# Boost_Converter_10V.net
KiCad netlist of a schematic drawn in Altium Designer
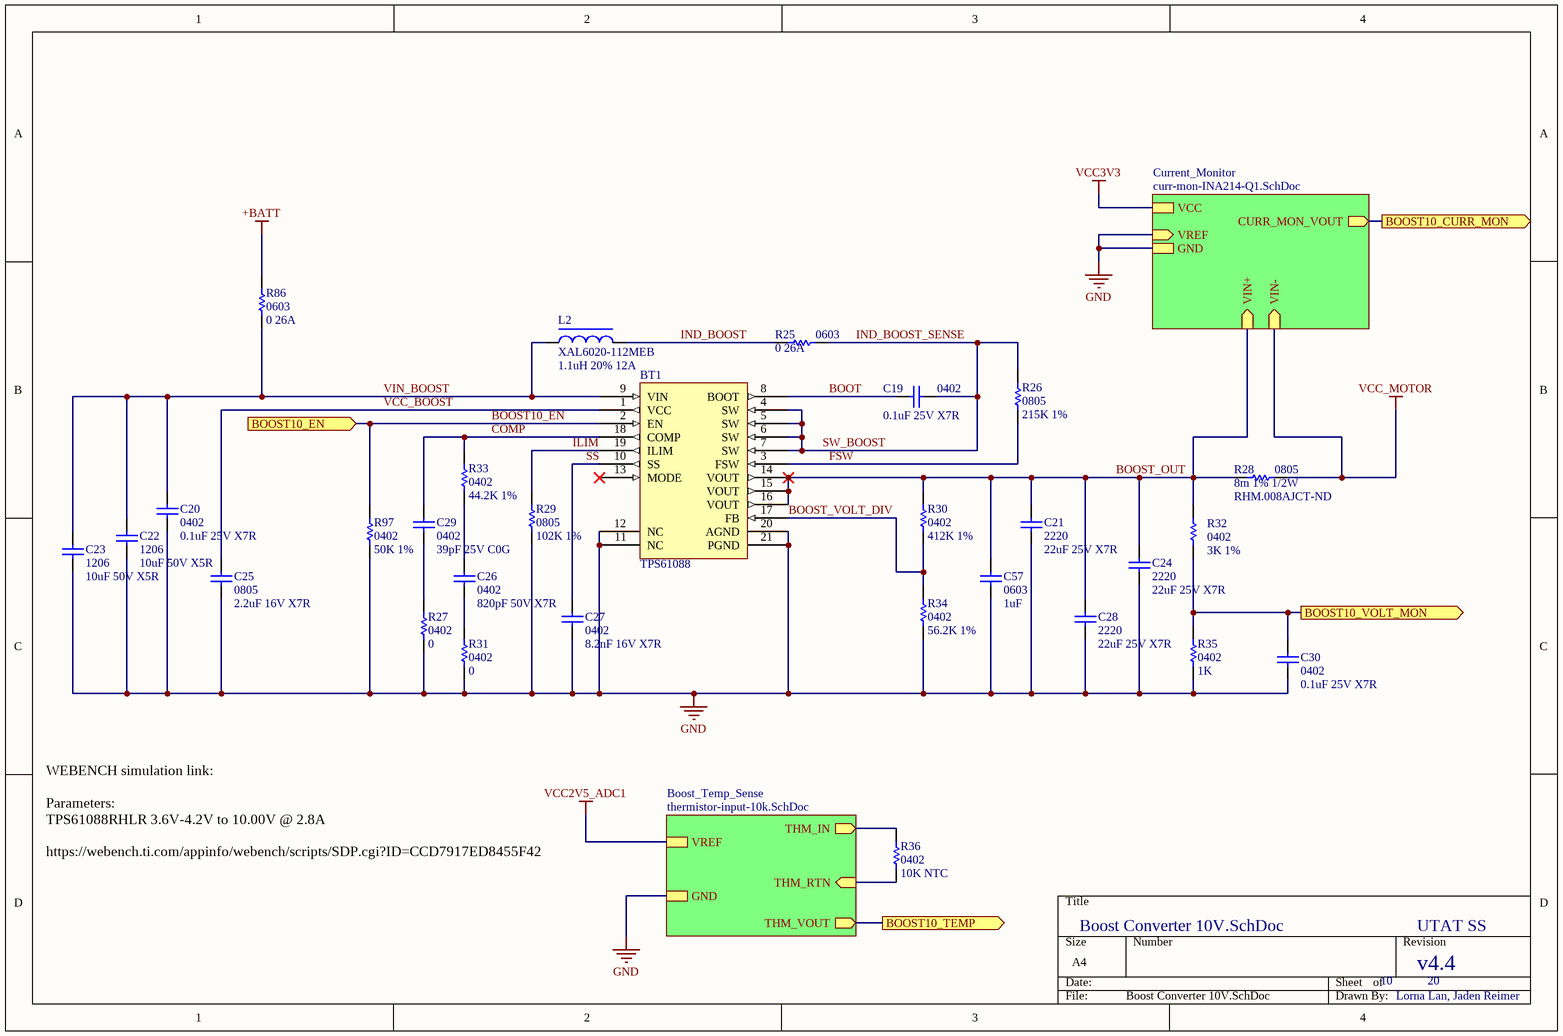
[diagram p0: Boost Converter 10V.SchDoc]

(export (version "E")
  (design (tool "Eeschema 10.0.6"))
  (components
    (comp (ref "BT1")
      (value "TPS61088")
      (footprint "QFN50P450X350X100-21N")
      (description "Boost converter")
      (libsource (lib "EPS") (part "TPS61088"))
    )
    (comp (ref "C19")
      (value "0402")
      (footprint "CAP0402R")
      (description "0402 capacitor")
      (fields (field (name "ALTIUM_VALUE") "0.1uF 25V X7R"))
      (libsource (lib "heron-general") (part "CAP0402"))
    )
    (comp (ref "C20")
      (value "0402")
      (footprint "CAP0402R")
      (description "0402 capacitor")
      (fields (field (name "ALTIUM_VALUE") "0.1uF 25V X7R"))
      (libsource (lib "heron-general") (part "CAP0402"))
    )
    (comp (ref "C21")
      (value "2220")
      (footprint "CAP2220")
      (description "Ceramic Capacitor 2220 (5750 Metric)")
      (fields (field (name "ALTIUM_VALUE") "22uF 25V X7R"))
      (libsource (lib "CAP2220") (part "CAP2220"))
    )
    (comp (ref "C22")
      (value "1206")
      (footprint "CAP1206R")
      (description "1206 capacitor")
      (fields (field (name "ALTIUM_VALUE") "10uF 50V X5R"))
      (libsource (lib "CAP1206") (part "CAP1206"))
    )
    (comp (ref "C23")
      (value "1206")
      (footprint "CAP1206R")
      (description "1206 capacitor")
      (fields (field (name "ALTIUM_VALUE") "10uF 50V X5R"))
      (libsource (lib "CAP1206") (part "CAP1206"))
    )
    (comp (ref "C24")
      (value "2220")
      (footprint "CAP2220")
      (description "Ceramic Capacitor 2220 (5750 Metric)")
      (fields (field (name "ALTIUM_VALUE") "22uF 25V X7R"))
      (libsource (lib "CAP2220") (part "CAP2220"))
    )
    (comp (ref "C25")
      (value "0805")
      (footprint "CAP0805R")
      (description "0805 capacitor")
      (fields (field (name "ALTIUM_VALUE") "2.2uF 16V X7R"))
      (libsource (lib "heron-general") (part "CAP0805"))
    )
    (comp (ref "C26")
      (value "0402")
      (footprint "CAP0402R")
      (description "0402 capacitor")
      (fields (field (name "ALTIUM_VALUE") "820pF 50V X7R"))
      (libsource (lib "CAP0402") (part "CAP0402"))
    )
    (comp (ref "C27")
      (value "0402")
      (footprint "CAP0402R")
      (description "0402 capacitor")
      (fields (field (name "ALTIUM_VALUE") "8.2nF 16V X7R"))
      (libsource (lib "CAP0402") (part "CAP0402"))
    )
    (comp (ref "C28")
      (value "2220")
      (footprint "CAP2220")
      (description "Ceramic Capacitor 2220 (5750 Metric)")
      (fields (field (name "ALTIUM_VALUE") "22uF 25V X7R"))
      (libsource (lib "CAP2220") (part "CAP2220"))
    )
    (comp (ref "C29")
      (value "0402")
      (footprint "CAP0402R")
      (description "0402 capacitor")
      (fields (field (name "ALTIUM_VALUE") "39pF 25V C0G"))
      (libsource (lib "CAP0402") (part "CAP0402"))
    )
    (comp (ref "C30")
      (value "0402")
      (footprint "CAP0402R")
      (description "0402 capacitor")
      (fields (field (name "ALTIUM_VALUE") "0.1uF 25V X7R"))
      (libsource (lib "heron-general") (part "CAP0402"))
    )
    (comp (ref "C57")
      (value "0603")
      (footprint "CAP0603R")
      (description "0603 capacitor")
      (fields
        (field (name "ALTIUM_VALUE") "1uF")
        (field (name "MANUFACTURER") "KEMET")
        (field (name "MANUFACTURER PART NUMBER") "C0603C105K4RACAUTO")
      )
      (libsource (lib "heron-general") (part "CAP0603"))
    )
    (comp (ref "L2")
      (value "XAL6020-112MEB")
      (footprint "XAL6020-112MEB")
      (description "Fixed Inductors 1.1uH 20% 12A, 13.1mOhms AEC-Q200")
      (fields (field (name "ALTIUM_VALUE") "1.1uH 20% 12A"))
      (libsource (lib "heron-general") (part "XAL6020-112MEB"))
    )
    (comp (ref "R25")
      (value "0603")
      (footprint "RES0603R")
      (description "0603 resistor")
      (fields (field (name "ALTIUM_VALUE") "0 26A"))
      (libsource (lib "heron-general") (part "RES0603"))
    )
    (comp (ref "R26")
      (value "0805")
      (footprint "RES0805R")
      (description "0805 resistor")
      (fields (field (name "ALTIUM_VALUE") "215K 1%"))
      (libsource (lib "RES0805") (part "RES0805"))
    )
    (comp (ref "R27")
      (value "0402")
      (footprint "RES0402R")
      (description "0402 resistor")
      (fields
        (field (name "ALTIUM_VALUE") "0")
        (field (name "MANUFACTURER") "Panasonic")
        (field (name "MANUFACTURER PART NUMBER") "ERJ-2GE0R00X")
      )
      (libsource (lib "heron-general") (part "RES0402"))
    )
    (comp (ref "R28")
      (value "0805")
      (footprint "RES0805R")
      (description "0805 resistor")
      (fields
        (field (name "ALTIUM_VALUE") "8m 1% 1/2W")
        (field (name "SUPPLIER PART NUMBER 1") "RHM.008AJCT-ND")
      )
      (libsource (lib "RES0805") (part "RES0805"))
    )
    (comp (ref "R29")
      (value "0805")
      (footprint "RES0805R")
      (description "0805 resistor")
      (fields (field (name "ALTIUM_VALUE") "102K 1%"))
      (libsource (lib "RES0805") (part "RES0805"))
    )
    (comp (ref "R30")
      (value "0402")
      (footprint "RES0402R")
      (description "0402 resistor")
      (fields (field (name "ALTIUM_VALUE") "412K 1%"))
      (libsource (lib "RES0402") (part "RES0402"))
    )
    (comp (ref "R31")
      (value "0402")
      (footprint "RES0402R")
      (description "0402 resistor")
      (fields
        (field (name "ALTIUM_VALUE") "0")
        (field (name "MANUFACTURER") "Panasonic")
        (field (name "MANUFACTURER PART NUMBER") "ERJ-2GE0R00X")
      )
      (libsource (lib "heron-general") (part "RES0402"))
    )
    (comp (ref "R32")
      (value "0402")
      (footprint "RES0402R")
      (description "0402 resistor")
      (fields (field (name "ALTIUM_VALUE") "3K 1%"))
      (libsource (lib "RES0402") (part "RES0402"))
    )
    (comp (ref "R33")
      (value "0402")
      (footprint "RES0402R")
      (description "0402 resistor")
      (fields (field (name "ALTIUM_VALUE") "44.2K 1%"))
      (libsource (lib "heron-general") (part "RES0402"))
    )
    (comp (ref "R34")
      (value "0402")
      (footprint "RES0402R")
      (description "0402 resistor")
      (fields (field (name "ALTIUM_VALUE") "56.2K 1%"))
      (libsource (lib "RES0402") (part "RES0402"))
    )
    (comp (ref "R35")
      (value "0402")
      (footprint "RES0402R")
      (description "0402 resistor")
      (fields (field (name "ALTIUM_VALUE") "1K"))
      (libsource (lib "RES0402") (part "RES0402"))
    )
    (comp (ref "R36")
      (value "0402")
      (footprint "RES0402R")
      (description "0402 resistor")
      (fields (field (name "ALTIUM_VALUE") "10K NTC"))
      (libsource (lib "heron-general") (part "RES0402"))
    )
    (comp (ref "R86")
      (value "0603")
      (footprint "RES0603R")
      (description "0603 resistor")
      (fields (field (name "ALTIUM_VALUE") "0 26A"))
      (libsource (lib "heron-general") (part "RES0603"))
    )
    (comp (ref "R97")
      (value "0402")
      (footprint "RES0402R")
      (description "0402 resistor")
      (fields (field (name "ALTIUM_VALUE") "50K 1%"))
      (libsource (lib "heron-general") (part "RES0402"))
    )
  )
  (nets
    (net (code "1") (name "+BATT") (class "Default")
      (node (ref "R86") (pin "2") (pinfunction "2_2") (pintype "passive"))
    )
    (net (code "3") (name "/BOOST10_EN") (class "Default")
      (node (ref "BT1") (pin "2") (pinfunction "EN_2") (pintype "input"))
      (node (ref "R97") (pin "2") (pinfunction "2_2") (pintype "passive"))
    )
    (net (code "5") (name "/BOOST10_VOLT_MON") (class "Default")
      (node (ref "C30") (pin "2") (pinfunction "2_2") (pintype "passive"))
      (node (ref "R32") (pin "1") (pinfunction "1_1") (pintype "passive"))
      (node (ref "R35") (pin "2") (pinfunction "2_2") (pintype "passive"))
    )
    (net (code "6") (name "/BOOST_OUT") (class "Default")
      (node (ref "BT1") (pin "14") (pinfunction "VOUT_14") (pintype "output"))
      (node (ref "BT1") (pin "15") (pinfunction "VOUT_15") (pintype "output"))
      (node (ref "BT1") (pin "16") (pinfunction "VOUT_16") (pintype "output"))
      (node (ref "C21") (pin "2") (pinfunction "2_2") (pintype "passive"))
      (node (ref "C24") (pin "2") (pinfunction "2_2") (pintype "passive"))
      (node (ref "C28") (pin "2") (pinfunction "2_2") (pintype "passive"))
      (node (ref "C57") (pin "2") (pinfunction "2_2") (pintype "passive"))
      (node (ref "R28") (pin "1") (pinfunction "1_1") (pintype "passive"))
      (node (ref "R30") (pin "2") (pinfunction "2_2") (pintype "passive"))
      (node (ref "R32") (pin "2") (pinfunction "2_2") (pintype "passive"))
    )
    (net (code "7") (name "/BOOST_VOLT_DIV") (class "Default")
      (node (ref "BT1") (pin "17") (pinfunction "FB_17") (pintype "input"))
      (node (ref "R30") (pin "1") (pinfunction "1_1") (pintype "passive"))
      (node (ref "R34") (pin "2") (pinfunction "2_2") (pintype "passive"))
    )
    (net (code "8") (name "/BOOT") (class "Default")
      (node (ref "BT1") (pin "8") (pinfunction "BOOT_8") (pintype "output"))
      (node (ref "C19") (pin "2") (pinfunction "2_2") (pintype "passive"))
    )
    (net (code "9") (name "/COMP") (class "Default")
      (node (ref "BT1") (pin "18") (pinfunction "COMP_18") (pintype "output"))
      (node (ref "C29") (pin "2") (pinfunction "2_2") (pintype "passive"))
      (node (ref "R33") (pin "2") (pinfunction "2_2") (pintype "passive"))
    )
    (net (code "10") (name "/FSW") (class "Default")
      (node (ref "BT1") (pin "3") (pinfunction "FSW_3") (pintype "input"))
      (node (ref "R26") (pin "1") (pinfunction "1_1") (pintype "passive"))
    )
    (net (code "11") (name "/ILIM") (class "Default")
      (node (ref "BT1") (pin "19") (pinfunction "ILIM_19") (pintype "output"))
      (node (ref "R29") (pin "2") (pinfunction "2_2") (pintype "passive"))
    )
    (net (code "12") (name "/IND_BOOST") (class "Default")
      (node (ref "L2") (pin "2") (pinfunction "2_2") (pintype "passive"))
      (node (ref "R25") (pin "1") (pinfunction "1_1") (pintype "passive"))
    )
    (net (code "13") (name "/IND_BOOST_SENSE") (class "Default")
      (node (ref "BT1") (pin "4") (pinfunction "SW_4") (pintype "input"))
      (node (ref "BT1") (pin "5") (pinfunction "SW_5") (pintype "input"))
      (node (ref "BT1") (pin "6") (pinfunction "SW_6") (pintype "input"))
      (node (ref "BT1") (pin "7") (pinfunction "SW_7") (pintype "input"))
      (node (ref "C19") (pin "1") (pinfunction "1_1") (pintype "passive"))
      (node (ref "R25") (pin "2") (pinfunction "2_2") (pintype "passive"))
      (node (ref "R26") (pin "2") (pinfunction "2_2") (pintype "passive"))
    )
    (net (code "14") (name "/SS") (class "Default")
      (node (ref "BT1") (pin "10") (pinfunction "SS_10") (pintype "output"))
      (node (ref "C27") (pin "2") (pinfunction "2_2") (pintype "passive"))
    )
    (net (code "15") (name "/THM_IN") (class "Default")
      (node (ref "R36") (pin "2") (pinfunction "2_2") (pintype "passive"))
    )
    (net (code "16") (name "/THM_RTN") (class "Default")
      (node (ref "R36") (pin "1") (pinfunction "1_1") (pintype "passive"))
    )
    (net (code "17") (name "/VCC_BOOST") (class "Default")
      (node (ref "BT1") (pin "1") (pinfunction "VCC_1") (pintype "output"))
      (node (ref "C25") (pin "2") (pinfunction "2_2") (pintype "passive"))
    )
    (net (code "18") (name "/VIN_BOOST") (class "Default")
      (node (ref "BT1") (pin "9") (pinfunction "VIN_9") (pintype "input"))
      (node (ref "C20") (pin "2") (pinfunction "2_2") (pintype "passive"))
      (node (ref "C22") (pin "2") (pinfunction "2_2") (pintype "passive"))
      (node (ref "C23") (pin "2") (pinfunction "2_2") (pintype "passive"))
      (node (ref "L2") (pin "1") (pinfunction "1_1") (pintype "passive"))
      (node (ref "R86") (pin "1") (pinfunction "1_1") (pintype "passive"))
    )
    (net (code "19") (name "GND") (class "Default")
      (node (ref "BT1") (pin "11") (pinfunction "NC_11") (pintype "passive"))
      (node (ref "BT1") (pin "12") (pinfunction "NC_12") (pintype "passive"))
      (node (ref "BT1") (pin "20") (pinfunction "AGND_20") (pintype "power_in"))
      (node (ref "BT1") (pin "21") (pinfunction "PGND_21") (pintype "power_in"))
      (node (ref "C20") (pin "1") (pinfunction "1_1") (pintype "passive"))
      (node (ref "C21") (pin "1") (pinfunction "1_1") (pintype "passive"))
      (node (ref "C22") (pin "1") (pinfunction "1_1") (pintype "passive"))
      (node (ref "C23") (pin "1") (pinfunction "1_1") (pintype "passive"))
      (node (ref "C24") (pin "1") (pinfunction "1_1") (pintype "passive"))
      (node (ref "C25") (pin "1") (pinfunction "1_1") (pintype "passive"))
      (node (ref "C27") (pin "1") (pinfunction "1_1") (pintype "passive"))
      (node (ref "C28") (pin "1") (pinfunction "1_1") (pintype "passive"))
      (node (ref "C30") (pin "1") (pinfunction "1_1") (pintype "passive"))
      (node (ref "C57") (pin "1") (pinfunction "1_1") (pintype "passive"))
      (node (ref "R27") (pin "1") (pinfunction "1_1") (pintype "passive"))
      (node (ref "R29") (pin "1") (pinfunction "1_1") (pintype "passive"))
      (node (ref "R31") (pin "1") (pinfunction "1_1") (pintype "passive"))
      (node (ref "R34") (pin "1") (pinfunction "1_1") (pintype "passive"))
      (node (ref "R35") (pin "1") (pinfunction "1_1") (pintype "passive"))
      (node (ref "R97") (pin "1") (pinfunction "1_1") (pintype "passive"))
    )
    (net (code "20") (name "Net-(C26-Pad1)") (class "Default")
      (node (ref "C26") (pin "1") (pinfunction "1_1") (pintype "passive"))
      (node (ref "R31") (pin "2") (pinfunction "2_2") (pintype "passive"))
    )
    (net (code "21") (name "Net-(C26-Pad2)") (class "Default")
      (node (ref "C26") (pin "2") (pinfunction "2_2") (pintype "passive"))
      (node (ref "R33") (pin "1") (pinfunction "1_1") (pintype "passive"))
    )
    (net (code "22") (name "Net-(C29-Pad1)") (class "Default")
      (node (ref "C29") (pin "1") (pinfunction "1_1") (pintype "passive"))
      (node (ref "R27") (pin "2") (pinfunction "2_2") (pintype "passive"))
    )
    (net (code "25") (name "VCC_MOTOR") (class "Default")
      (node (ref "R28") (pin "2") (pinfunction "2_2") (pintype "passive"))
    )
    (net (code "26") (name "unconnected-(BT1-MODE-Pad13)") (class "Default")
      (node (ref "BT1") (pin "13") (pinfunction "MODE_13") (pintype "input+no_connect"))
    )
  )
)
